# SmartRock_MS5803_Breakout.net
KiCad netlist of a schematic drawn in EAGLE
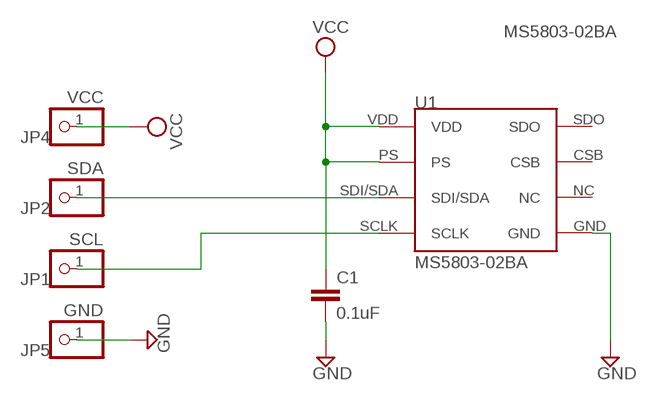
[diagram p0: schematic, sheet 1]

(export (version "E")
  (design (tool "Eeschema 10.0.6"))
  (components
    (comp (ref "C1")
      (value "0.1uF")
      (footprint "eagle-import:C0805")
      (libsource (lib "eagle-import") (part "C-EUC0805"))
    )
    (comp (ref "JP1")
      (value "SCL")
      (footprint "eagle-import:1X01")
      (libsource (lib "eagle-import") (part "PINHD-1X1"))
    )
    (comp (ref "JP2")
      (value "SDA")
      (footprint "eagle-import:1X01")
      (libsource (lib "eagle-import") (part "PINHD-1X1"))
    )
    (comp (ref "JP4")
      (value "VCC")
      (footprint "eagle-import:1X01")
      (libsource (lib "eagle-import") (part "PINHD-1X1"))
    )
    (comp (ref "JP5")
      (value "GND")
      (footprint "eagle-import:1X01")
      (libsource (lib "eagle-import") (part "PINHD-1X1"))
    )
    (comp (ref "U1")
      (value "MS5803-02BA")
      (footprint "eagle-import:MS5803-02BA")
      (libsource (lib "eagle-import") (part "MS5803-02BA"))
    )
  )
  (nets
    (net (code "1") (name "GND") (class "Default")
      (node (ref "C1") (pin "2") (pinfunction "2_2") (pintype "passive"))
      (node (ref "JP5") (pin "1") (pinfunction "1_1") (pintype "passive"))
      (node (ref "U1") (pin "GND") (pinfunction "GND_GND") (pintype "bidirectional"))
    )
    (net (code "2") (name "Net-(JP1-Pad1)") (class "Default")
      (node (ref "JP1") (pin "1") (pinfunction "1_1") (pintype "passive"))
      (node (ref "U1") (pin "SCLK") (pinfunction "SCLK_SCLK") (pintype "bidirectional"))
    )
    (net (code "3") (name "Net-(JP2-Pad1)") (class "Default")
      (node (ref "JP2") (pin "1") (pinfunction "1_1") (pintype "passive"))
      (node (ref "U1") (pin "SDI/SDA") (pinfunction "SDI/SDA_SDI/SDA") (pintype "bidirectional"))
    )
    (net (code "4") (name "VCC") (class "Default")
      (node (ref "C1") (pin "1") (pinfunction "1_1") (pintype "passive"))
      (node (ref "JP4") (pin "1") (pinfunction "1_1") (pintype "passive"))
      (node (ref "U1") (pin "PS") (pinfunction "PS_PS") (pintype "bidirectional"))
      (node (ref "U1") (pin "VDD") (pinfunction "VDD_VDD") (pintype "bidirectional"))
    )
    (net (code "5") (name "unconnected-(U1-PadCSB)") (class "Default")
      (node (ref "U1") (pin "CSB") (pinfunction "CSB_CSB") (pintype "bidirectional"))
    )
    (net (code "6") (name "unconnected-(U1-PadNC)") (class "Default")
      (node (ref "U1") (pin "NC") (pinfunction "NC_NC") (pintype "bidirectional"))
    )
    (net (code "7") (name "unconnected-(U1-PadSDO)") (class "Default")
      (node (ref "U1") (pin "SDO") (pinfunction "SDO_SDO") (pintype "bidirectional"))
    )
  )
)
